# SummingAmplifier.net
KiCad netlist of a schematic drawn in Altium Designer
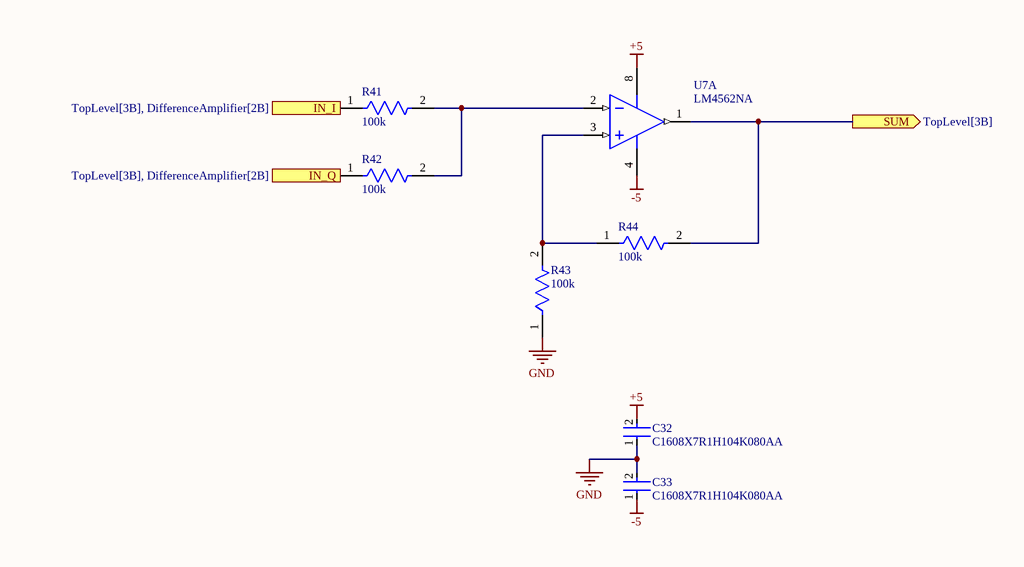
[diagram p0: SummingAmplifier.SchDoc]

(export (version "E")
  (design (tool "Eeschema 10.0.6"))
  (components
    (comp (ref "C32")
      (value "C1608X7R1H104K080AA")
      (footprint "FP-C1608-080-0_1-MFG")
      (description "Multilayer Ceramic Capacitors 100nF ±10% 50V X7R SMD 0603")
      (fields (field (name "VOLTAGE") "50V") (field (name "TOLERANCE") "10%"))
      (libsource (lib "Altium Content Vault") (part "236180d848d6139a670b325ea6854c9"))
    )
    (comp (ref "C33")
      (value "C1608X7R1H104K080AA")
      (footprint "FP-C1608-080-0_1-MFG")
      (description "Multilayer Ceramic Capacitors 100nF ±10% 50V X7R SMD 0603")
      (fields (field (name "VOLTAGE") "50V") (field (name "TOLERANCE") "10%"))
      (libsource (lib "Altium Content Vault") (part "236180d848d6139a670b325ea6854c9"))
    )
    (comp (ref "R41")
      (value "100k")
      (footprint "FP-RC0805-0_6-IPC_C")
      (description "RES 100K OHM 1% 1/8W 0805")
      (fields (field (name "TOLERANCE") "1%"))
      (libsource (lib "Altium Content Vault") (part "1029c3af85768c4190bb7ad29bc67b5"))
    )
    (comp (ref "R42")
      (value "100k")
      (footprint "FP-RC0805-0_6-IPC_C")
      (description "RES 100K OHM 1% 1/8W 0805")
      (fields (field (name "TOLERANCE") "1%"))
      (libsource (lib "Altium Content Vault") (part "1029c3af85768c4190bb7ad29bc67b5"))
    )
    (comp (ref "R43")
      (value "100k")
      (footprint "FP-RC0805-0_6-IPC_C")
      (description "RES 100K OHM 1% 1/8W 0805")
      (fields (field (name "TOLERANCE") "1%"))
      (libsource (lib "Altium Content Vault") (part "1029c3af85768c4190bb7ad29bc67b5"))
    )
    (comp (ref "R44")
      (value "100k")
      (footprint "FP-RC0805-0_6-IPC_C")
      (description "RES 100K OHM 1% 1/8W 0805")
      (fields (field (name "TOLERANCE") "1%"))
      (libsource (lib "Altium Content Vault") (part "1029c3af85768c4190bb7ad29bc67b5"))
    )
    (comp (ref "U7")
      (value "LM4562NA")
      (footprint "N08E")
      (description "Dual High Performance, High Fidelity Audio Operational Amplifier, 8-pin MDIP")
      (fields (field (name "MANUFACTURER") "National Semiconductor"))
      (libsource (lib "Altium Content Vault") (part "AMP-AUDA-LM4562-8"))
    )
  )
  (nets
    (net (code "1") (name "+5") (class "Default")
      (node (ref "C32") (pin "2") (pinfunction "2_2") (pintype "passive"))
      (node (ref "U7") (pin "8") (pinfunction "V+_8") (pintype "power_in"))
    )
    (net (code "2") (name "-5") (class "Default")
      (node (ref "C33") (pin "1") (pinfunction "1_1") (pintype "passive"))
      (node (ref "U7") (pin "4") (pinfunction "V-_4") (pintype "power_in"))
    )
    (net (code "3") (name "/IN_I") (class "Default")
      (node (ref "R41") (pin "1") (pinfunction "1_1") (pintype "passive"))
    )
    (net (code "4") (name "/IN_Q") (class "Default")
      (node (ref "R42") (pin "1") (pinfunction "1_1") (pintype "passive"))
    )
    (net (code "5") (name "/SUM") (class "Default")
      (node (ref "R44") (pin "2") (pinfunction "2_2") (pintype "passive"))
      (node (ref "U7") (pin "1") (pinfunction "OUT_A_1") (pintype "output"))
    )
    (net (code "6") (name "GND") (class "Default")
      (node (ref "C32") (pin "1") (pinfunction "1_1") (pintype "passive"))
      (node (ref "C33") (pin "2") (pinfunction "2_2") (pintype "passive"))
      (node (ref "R43") (pin "1") (pinfunction "1_1") (pintype "passive"))
    )
    (net (code "7") (name "Net-(R41-Pad2)") (class "Default")
      (node (ref "R41") (pin "2") (pinfunction "2_2") (pintype "passive"))
      (node (ref "R42") (pin "2") (pinfunction "2_2") (pintype "passive"))
      (node (ref "U7") (pin "2") (pinfunction "IN_A_2") (pintype "input"))
    )
    (net (code "8") (name "Net-(R43-Pad2)") (class "Default")
      (node (ref "R43") (pin "2") (pinfunction "2_2") (pintype "passive"))
      (node (ref "R44") (pin "1") (pinfunction "1_1") (pintype "passive"))
      (node (ref "U7") (pin "3") (pinfunction "IN_A_3") (pintype "input"))
    )
  )
)
